# Radio.net
KiCad netlist of a schematic drawn in Altium Designer
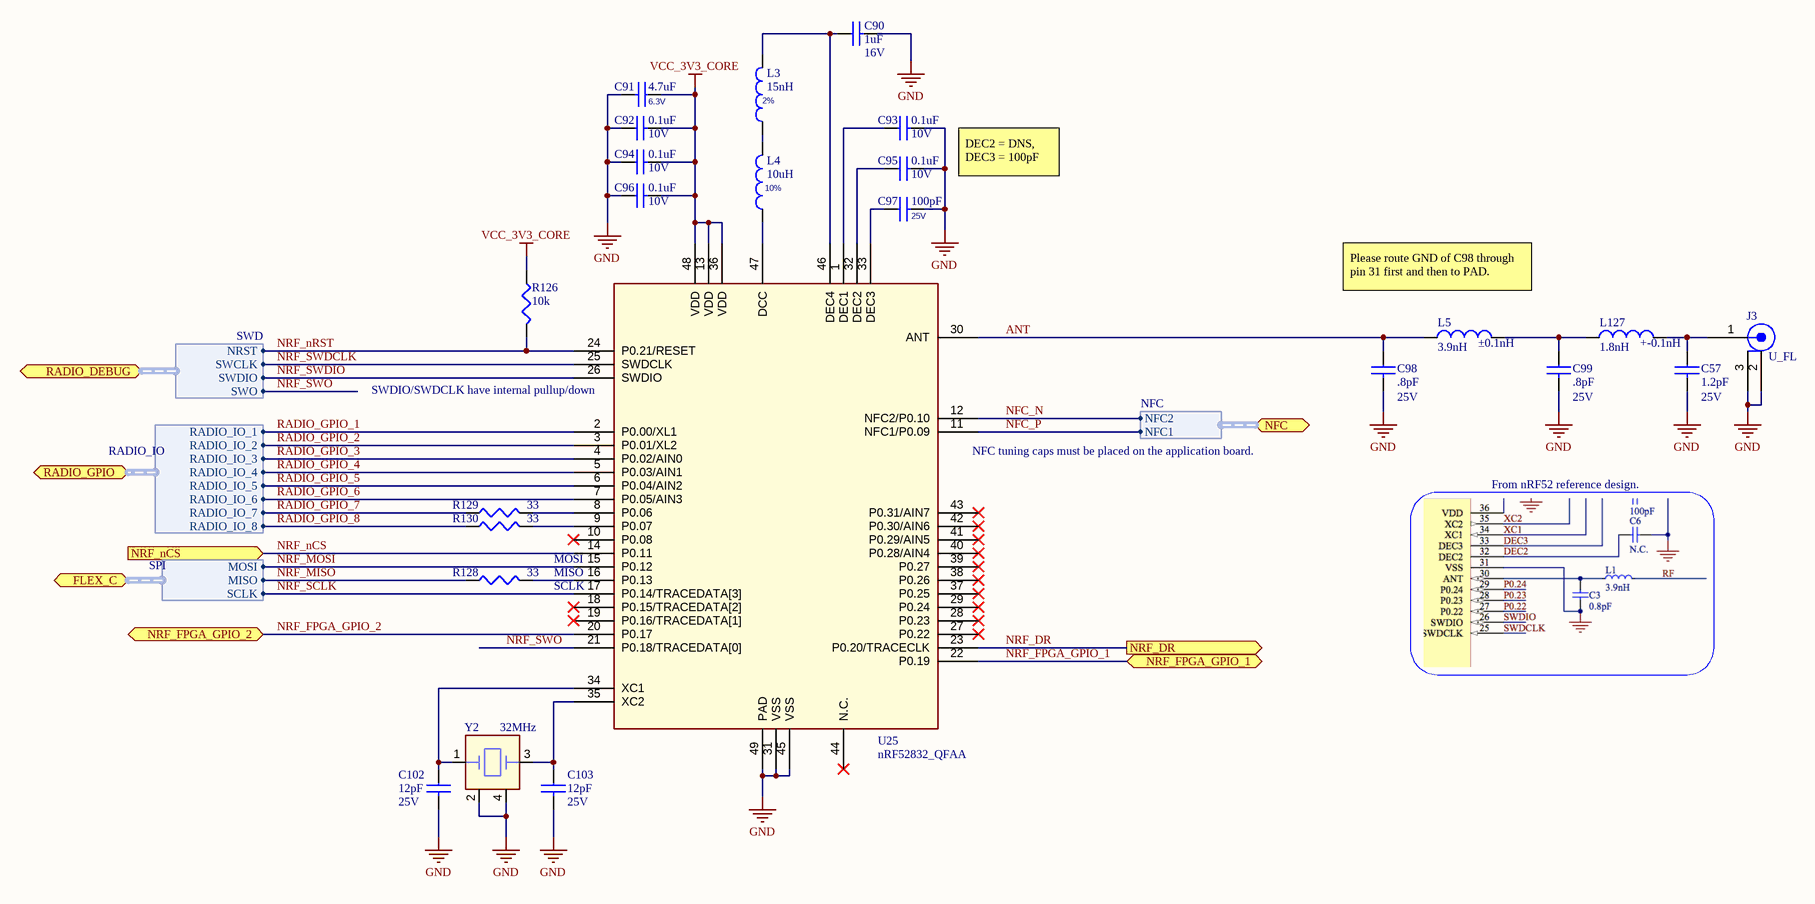
[diagram p0: Radio.SchDoc]

(export (version "E")
  (design (tool "Eeschema 10.0.6"))
  (components
    (comp (ref "C57")
      (value "1.2pF")
      (footprint "0201-IPCsm_33")
      (description "Multilayer Ceramic Capacitors MLCC - SMD/SMT 0201 1.2pF 25Volts C0G +/-0.1pF")
      (fields
        (field (name "VOLTAGE") "25V")
        (field (name "MFG") "Murata")
        (field (name "TOLERANCE") "±0.1pF")
      )
      (libsource (lib "SynapseLibrary") (part "CAP"))
    )
    (comp (ref "C90")
      (value "1uF")
      (footprint "0402-IPCsm_55")
      (description "CAP CER 1UF 16V X5R 0402")
      (fields
        (field (name "VOLTAGE") "16V")
        (field (name "MFG") "Samsung Electro-Mechanics America, Inc.")
        (field (name "TOLERANCE") "1%")
      )
      (libsource (lib "SynapseLibrary") (part "CAP"))
    )
    (comp (ref "C91")
      (value "4.7uF")
      (footprint "0402-IPCsm_55")
      (description "CAP CER 4.7UF 6.3V 20% X5R 0402")
      (fields (field (name "VOLTAGE") "6.3V") (field (name "MFG") "MURATA") (field (name "TOLERANCE") "20%"))
      (libsource (lib "SynapseLibrary") (part "CAP"))
    )
    (comp (ref "C92")
      (value "0.1uF")
      (footprint "0201-IPCsm_33")
      (description "CAP CER 0.1UF 10V 10% X5R 0201")
      (fields
        (field (name "VOLTAGE") "10V")
        (field (name "MFG") "Samsung Electro-Mechanics America, Inc")
        (field (name "TOLERANCE") "10%")
      )
      (libsource (lib "SynapseLibrary") (part "CAP"))
    )
    (comp (ref "C93")
      (value "0.1uF")
      (footprint "0201-IPCsm_33")
      (description "CAP CER 0.1UF 10V 10% X5R 0201")
      (fields
        (field (name "VOLTAGE") "10V")
        (field (name "MFG") "Samsung Electro-Mechanics America, Inc")
        (field (name "TOLERANCE") "10%")
      )
      (libsource (lib "SynapseLibrary") (part "CAP"))
    )
    (comp (ref "C94")
      (value "0.1uF")
      (footprint "0201-IPCsm_33")
      (description "CAP CER 0.1UF 10V 10% X5R 0201")
      (fields
        (field (name "VOLTAGE") "10V")
        (field (name "MFG") "Samsung Electro-Mechanics America, Inc")
        (field (name "TOLERANCE") "10%")
      )
      (libsource (lib "SynapseLibrary") (part "CAP"))
    )
    (comp (ref "C95")
      (value "0.1uF")
      (footprint "0201-IPCsm_33")
      (description "CAP CER 0.1UF 10V 10% X5R 0201")
      (fields
        (field (name "VOLTAGE") "10V")
        (field (name "MFG") "Samsung Electro-Mechanics America, Inc")
        (field (name "TOLERANCE") "10%")
      )
      (libsource (lib "SynapseLibrary") (part "CAP"))
    )
    (comp (ref "C96")
      (value "0.1uF")
      (footprint "0201-IPCsm_33")
      (description "CAP CER 0.1UF 10V 10% X5R 0201")
      (fields
        (field (name "VOLTAGE") "10V")
        (field (name "MFG") "Samsung Electro-Mechanics America, Inc")
        (field (name "TOLERANCE") "10%")
      )
      (libsource (lib "SynapseLibrary") (part "CAP"))
    )
    (comp (ref "C97")
      (value "100pF")
      (footprint "0201-IPCsm_33")
      (description "CAP CER 100PF 25V 5% NP0 0201")
      (fields (field (name "VOLTAGE") "25V") (field (name "MFG") "MURATA") (field (name "TOLERANCE") "5%"))
      (libsource (lib "SynapseLibrary") (part "CAP"))
    )
    (comp (ref "C98")
      (value ".8pF")
      (footprint "0201-IPCsm_33")
      (fields
        (field (name "VOLTAGE") "25V")
        (field (name "MFG") "Murata Electronics North America")
        (field (name "TOLERANCE") "0.05pF")
      )
      (libsource (lib "SynapseLibrary") (part "CAP"))
    )
    (comp (ref "C99")
      (value ".8pF")
      (footprint "0201-IPCsm_33")
      (description "CAP CER 0.8PF 25V NP0 0201")
      (fields
        (field (name "VOLTAGE") "25V")
        (field (name "MFG") "TDK Corporation")
        (field (name "TOLERANCE") "0.05pF")
      )
      (libsource (lib "SynapseLibrary") (part "CAP"))
    )
    (comp (ref "C102")
      (value "12pF")
      (footprint "0201-IPCsm_33")
      (description "12pF 25V Ceramic Capacitor C0G, NP0 0201")
      (fields (field (name "VOLTAGE") "25V") (field (name "MFG") "Murata") (field (name "TOLERANCE") "2%"))
      (libsource (lib "SynapseLibrary") (part "CAP"))
    )
    (comp (ref "C103")
      (value "12pF")
      (footprint "0201-IPCsm_33")
      (description "12pF 25V Ceramic Capacitor C0G, NP0 0201")
      (fields (field (name "VOLTAGE") "25V") (field (name "MFG") "Murata") (field (name "TOLERANCE") "2%"))
      (libsource (lib "SynapseLibrary") (part "CAP"))
    )
    (comp (ref "J3")
      (value "U_FL")
      (footprint "con_hrs_U_FL-SMT")
      (description "CONN RECPT ULTRA-MINI COAX SMD")
      (fields (field (name "MFG") "HIROSE"))
      (libsource (lib "SynapseLibrary") (part "CONNECTOR COAX-M 2GND"))
    )
    (comp (ref "L3")
      (value "15nH")
      (footprint "IND_0402-36_LQP15M")
      (description "IND, 15 nH, 2%, 0402")
      (fields (field (name "TOLERANCE") "2%") (field (name "MFG") "Murata"))
      (libsource (lib "SynapseLibrary") (part "IND_H"))
    )
    (comp (ref "L4")
      (value "10uH")
      (footprint "IND-0603_32H")
      (description "INDUCTOR 10UH 115MA 0603")
      (fields (field (name "TOLERANCE") "10%") (field (name "MFG") "Taiyo Yuden"))
      (libsource (lib "SynapseLibrary") (part "IND_H"))
    )
    (comp (ref "L5")
      (value "3.9nH")
      (footprint "0201-IPCsm_33")
      (description "FIXED IND 3.9NH 400MA 300 MOHM 0201")
      (fields (field (name "TOLERANCE") "±0.1nH") (field (name "MFG") "Murata"))
      (libsource (lib "SynapseLibrary") (part "IND_H"))
    )
    (comp (ref "L127")
      (value "1.8nH")
      (footprint "0201-IPCsm_33")
      (description "FIXED IND 1.8NH 600MA 150 MOHM")
      (fields (field (name "TOLERANCE") "+-0.1nH") (field (name "MFG") "MURATA"))
      (libsource (lib "SynapseLibrary") (part "IND_H"))
    )
    (comp (ref "R126")
      (value "10k")
      (footprint "0201-IPCsm_26")
      (description "RES 10K OHM 1/20W 1% 0201 SMD")
      (fields (field (name "TOLERANCE") "1.00%") (field (name "VOLTAGE") "50V"))
      (libsource (lib "SynapseLibrary") (part "RES"))
    )
    (comp (ref "R128")
      (value "33")
      (footprint "0201-IPCsm_26")
      (description "RES 33 OHM 1/20W 1% 0201 SMD")
      (fields (field (name "TOLERANCE") "1.00%") (field (name "VOLTAGE") "50V"))
      (libsource (lib "SynapseLibrary") (part "RES"))
    )
    (comp (ref "R129")
      (value "33")
      (footprint "0201-IPCsm_26")
      (description "RES 33 OHM 1/20W 1% 0201 SMD")
      (fields (field (name "TOLERANCE") "1.00%") (field (name "VOLTAGE") "50V"))
      (libsource (lib "SynapseLibrary") (part "RES"))
    )
    (comp (ref "R130")
      (value "33")
      (footprint "0201-IPCsm_26")
      (description "RES 33 OHM 1/20W 1% 0201 SMD")
      (fields (field (name "TOLERANCE") "1.00%") (field (name "VOLTAGE") "50V"))
      (libsource (lib "SynapseLibrary") (part "RES"))
    )
    (comp (ref "U25")
      (value "nRF52832_QFAA")
      (footprint "QFN48_6X6MM_NO_VIAS")
      (description "IC SOC 2.4GHZ 512K FLASH QFN")
      (fields
        (field (name "PART NUMBER") "nRF52832-QFAA")
        (field (name "MANUFACTURER") "Nordic Semiconductor")
        (field (name "PUBLISHER") "Nordic Semiconductor")
      )
      (libsource (lib "SynapseLibrary") (part "nRF52832_QFAA"))
    )
    (comp (ref "Y2")
      (value "32MHz")
      (footprint "Xtal_abm12")
      (description "Crystal 32.0000MHz 20ppm 8pF 100 Ohm -20°C - 70°C Surface Mount 4-SMD, No Lead (DFN, LCC)")
      (fields (field (name "MFG") "Abracon LLC") (field (name "TOLERANCE") "20ppm"))
      (libsource (lib "SynapseLibrary") (part "XTAL_2_GND_PIN"))
    )
  )
  (nets
    (net (code "5") (name "/ANT") (class "Default")
      (node (ref "C98") (pin "1") (pinfunction "1_1") (pintype "passive"))
      (node (ref "L5") (pin "1") (pinfunction "1_1") (pintype "passive"))
      (node (ref "U25") (pin "30") (pinfunction "ANT_30") (pintype "passive"))
    )
    (net (code "6") (name "/NFC_N") (class "Default")
      (node (ref "U25") (pin "12") (pinfunction "NFC2/P0.10_12") (pintype "passive"))
    )
    (net (code "7") (name "/NFC_P") (class "Default")
      (node (ref "U25") (pin "11") (pinfunction "NFC1/P0.09_11") (pintype "passive"))
    )
    (net (code "8") (name "/NRF_DR") (class "Default")
      (node (ref "U25") (pin "23") (pinfunction "P0.20/TRACECLK_23") (pintype "passive"))
    )
    (net (code "9") (name "/NRF_FPGA_GPIO_1") (class "Default")
      (node (ref "U25") (pin "22") (pinfunction "P0.19_22") (pintype "passive"))
    )
    (net (code "10") (name "/NRF_FPGA_GPIO_2") (class "Default")
      (node (ref "U25") (pin "20") (pinfunction "P0.17_20") (pintype "passive"))
    )
    (net (code "11") (name "/NRF_MISO") (class "Default")
      (node (ref "R128") (pin "1") (pinfunction "1_1") (pintype "passive"))
    )
    (net (code "12") (name "/NRF_MOSI") (class "Default")
      (node (ref "U25") (pin "15") (pinfunction "P0.12_15") (pintype "passive"))
    )
    (net (code "13") (name "/NRF_SCLK") (class "Default")
      (node (ref "U25") (pin "17") (pinfunction "P0.14/TRACEDATA[3]_17") (pintype "passive"))
    )
    (net (code "14") (name "/NRF_SWDCLK") (class "Default")
      (node (ref "U25") (pin "25") (pinfunction "SWDCLK_25") (pintype "passive"))
    )
    (net (code "15") (name "/NRF_SWDIO") (class "Default")
      (node (ref "U25") (pin "26") (pinfunction "SWDIO_26") (pintype "passive"))
    )
    (net (code "16") (name "/NRF_SWO") (class "Default")
      (node (ref "U25") (pin "21") (pinfunction "P0.18/TRACEDATA[0]_21") (pintype "passive"))
    )
    (net (code "17") (name "/NRF_nCS") (class "Default")
      (node (ref "U25") (pin "14") (pinfunction "P0.11_14") (pintype "passive"))
    )
    (net (code "18") (name "/NRF_nRST") (class "Default")
      (node (ref "R126") (pin "2") (pinfunction "2_2") (pintype "passive"))
      (node (ref "U25") (pin "24") (pinfunction "P0.21/RESET_24") (pintype "passive"))
    )
    (net (code "19") (name "/RADIO_GPIO_1") (class "Default")
      (node (ref "U25") (pin "2") (pinfunction "P0.00/XL1_2") (pintype "passive"))
    )
    (net (code "20") (name "/RADIO_GPIO_2") (class "Default")
      (node (ref "U25") (pin "3") (pinfunction "P0.01/XL2_3") (pintype "passive"))
    )
    (net (code "21") (name "/RADIO_GPIO_3") (class "Default")
      (node (ref "U25") (pin "4") (pinfunction "P0.02/AIN0_4") (pintype "passive"))
    )
    (net (code "22") (name "/RADIO_GPIO_4") (class "Default")
      (node (ref "U25") (pin "5") (pinfunction "P0.03/AIN1_5") (pintype "passive"))
    )
    (net (code "23") (name "/RADIO_GPIO_5") (class "Default")
      (node (ref "U25") (pin "6") (pinfunction "P0.04/AIN2_6") (pintype "passive"))
    )
    (net (code "24") (name "/RADIO_GPIO_6") (class "Default")
      (node (ref "U25") (pin "7") (pinfunction "P0.05/AIN3_7") (pintype "passive"))
    )
    (net (code "25") (name "/RADIO_GPIO_7") (class "Default")
      (node (ref "R129") (pin "1") (pinfunction "1_1") (pintype "passive"))
    )
    (net (code "26") (name "/RADIO_GPIO_8") (class "Default")
      (node (ref "R130") (pin "1") (pinfunction "1_1") (pintype "passive"))
    )
    (net (code "31") (name "GND") (class "Default")
      (node (ref "C102") (pin "2") (pinfunction "2_2") (pintype "passive"))
      (node (ref "C103") (pin "2") (pinfunction "2_2") (pintype "passive"))
      (node (ref "C57") (pin "2") (pinfunction "2_2") (pintype "passive"))
      (node (ref "C90") (pin "2") (pinfunction "2_2") (pintype "passive"))
      (node (ref "C91") (pin "2") (pinfunction "2_2") (pintype "passive"))
      (node (ref "C92") (pin "1") (pinfunction "1_1") (pintype "passive"))
      (node (ref "C93") (pin "2") (pinfunction "2_2") (pintype "passive"))
      (node (ref "C94") (pin "1") (pinfunction "1_1") (pintype "passive"))
      (node (ref "C95") (pin "2") (pinfunction "2_2") (pintype "passive"))
      (node (ref "C96") (pin "1") (pinfunction "1_1") (pintype "passive"))
      (node (ref "C97") (pin "2") (pinfunction "2_2") (pintype "passive"))
      (node (ref "C98") (pin "2") (pinfunction "2_2") (pintype "passive"))
      (node (ref "C99") (pin "2") (pinfunction "2_2") (pintype "passive"))
      (node (ref "J3") (pin "2") (pinfunction "SHIELD_2") (pintype "passive"))
      (node (ref "J3") (pin "3") (pinfunction "SHIELD2_3") (pintype "passive"))
      (node (ref "U25") (pin "31") (pinfunction "VSS_31") (pintype "passive"))
      (node (ref "U25") (pin "45") (pinfunction "VSS_45") (pintype "passive"))
      (node (ref "U25") (pin "49") (pinfunction "PAD_49") (pintype "passive"))
      (node (ref "Y2") (pin "2") (pinfunction "2_2") (pintype "passive"))
      (node (ref "Y2") (pin "4") (pinfunction "4_4") (pintype "passive"))
    )
    (net (code "32") (name "Net-(C99-Pad1)") (class "Default")
      (node (ref "C99") (pin "1") (pinfunction "1_1") (pintype "passive"))
      (node (ref "L127") (pin "1") (pinfunction "1_1") (pintype "passive"))
      (node (ref "L5") (pin "2") (pinfunction "2_2") (pintype "passive"))
    )
    (net (code "33") (name "Net-(J3-CENTER)") (class "Default")
      (node (ref "C57") (pin "1") (pinfunction "1_1") (pintype "passive"))
      (node (ref "J3") (pin "1") (pinfunction "CENTER_1") (pintype "passive"))
      (node (ref "L127") (pin "2") (pinfunction "2_2") (pintype "passive"))
    )
    (net (code "34") (name "Net-(L3-Pad1)") (class "Default")
      (node (ref "L3") (pin "1") (pinfunction "1_1") (pintype "passive"))
      (node (ref "L4") (pin "2") (pinfunction "2_2") (pintype "passive"))
    )
    (net (code "35") (name "Net-(U25-DCC)") (class "Default")
      (node (ref "L4") (pin "1") (pinfunction "1_1") (pintype "passive"))
      (node (ref "U25") (pin "47") (pinfunction "DCC_47") (pintype "passive"))
    )
    (net (code "36") (name "Net-(U25-DEC1)") (class "Default")
      (node (ref "C93") (pin "1") (pinfunction "1_1") (pintype "passive"))
      (node (ref "U25") (pin "1") (pinfunction "DEC1_1") (pintype "passive"))
    )
    (net (code "37") (name "Net-(U25-DEC2)") (class "Default")
      (node (ref "C95") (pin "1") (pinfunction "1_1") (pintype "passive"))
      (node (ref "U25") (pin "32") (pinfunction "DEC2_32") (pintype "passive"))
    )
    (net (code "38") (name "Net-(U25-DEC3)") (class "Default")
      (node (ref "C97") (pin "1") (pinfunction "1_1") (pintype "passive"))
      (node (ref "U25") (pin "33") (pinfunction "DEC3_33") (pintype "passive"))
    )
    (net (code "39") (name "Net-(U25-DEC4)") (class "Default")
      (node (ref "C90") (pin "1") (pinfunction "1_1") (pintype "passive"))
      (node (ref "L3") (pin "2") (pinfunction "2_2") (pintype "passive"))
      (node (ref "U25") (pin "46") (pinfunction "DEC4_46") (pintype "passive"))
    )
    (net (code "40") (name "Net-(U25-P0.06)") (class "Default")
      (node (ref "R129") (pin "2") (pinfunction "2_2") (pintype "passive"))
      (node (ref "U25") (pin "8") (pinfunction "P0.06_8") (pintype "passive"))
    )
    (net (code "41") (name "Net-(U25-P0.07)") (class "Default")
      (node (ref "R130") (pin "2") (pinfunction "2_2") (pintype "passive"))
      (node (ref "U25") (pin "9") (pinfunction "P0.07_9") (pintype "passive"))
    )
    (net (code "42") (name "Net-(U25-P0.13)") (class "Default")
      (node (ref "R128") (pin "2") (pinfunction "2_2") (pintype "passive"))
      (node (ref "U25") (pin "16") (pinfunction "P0.13_16") (pintype "passive"))
    )
    (net (code "43") (name "Net-(U25-XC1)") (class "Default")
      (node (ref "C102") (pin "1") (pinfunction "1_1") (pintype "passive"))
      (node (ref "U25") (pin "34") (pinfunction "XC1_34") (pintype "passive"))
      (node (ref "Y2") (pin "1") (pinfunction "1_1") (pintype "passive"))
    )
    (net (code "44") (name "Net-(U25-XC2)") (class "Default")
      (node (ref "C103") (pin "1") (pinfunction "1_1") (pintype "passive"))
      (node (ref "U25") (pin "35") (pinfunction "XC2_35") (pintype "passive"))
      (node (ref "Y2") (pin "3") (pinfunction "3_3") (pintype "passive"))
    )
    (net (code "45") (name "VCC_3V3_CORE") (class "Default")
      (node (ref "C91") (pin "1") (pinfunction "1_1") (pintype "passive"))
      (node (ref "C92") (pin "2") (pinfunction "2_2") (pintype "passive"))
      (node (ref "C94") (pin "2") (pinfunction "2_2") (pintype "passive"))
      (node (ref "C96") (pin "2") (pinfunction "2_2") (pintype "passive"))
      (node (ref "R126") (pin "1") (pinfunction "1_1") (pintype "passive"))
      (node (ref "U25") (pin "13") (pinfunction "VDD_13") (pintype "passive"))
      (node (ref "U25") (pin "36") (pinfunction "VDD_36") (pintype "passive"))
      (node (ref "U25") (pin "48") (pinfunction "VDD_48") (pintype "passive"))
    )
    (net (code "46") (name "unconnected-(U25-N.C.-Pad44)") (class "Default")
      (node (ref "U25") (pin "44") (pinfunction "N.C._44") (pintype "passive+no_connect"))
    )
    (net (code "47") (name "unconnected-(U25-P0.08-Pad10)") (class "Default")
      (node (ref "U25") (pin "10") (pinfunction "P0.08_10") (pintype "passive+no_connect"))
    )
    (net (code "48") (name "unconnected-(U25-P0.15{slash}TRACEDATA[2]-Pad18)") (class "Default")
      (node (ref "U25") (pin "18") (pinfunction "P0.15/TRACEDATA[2]_18") (pintype "passive+no_connect"))
    )
    (net (code "49") (name "unconnected-(U25-P0.16{slash}TRACEDATA[1]-Pad19)") (class "Default")
      (node (ref "U25") (pin "19") (pinfunction "P0.16/TRACEDATA[1]_19") (pintype "passive+no_connect"))
    )
    (net (code "50") (name "unconnected-(U25-P0.22-Pad27)") (class "Default")
      (node (ref "U25") (pin "27") (pinfunction "P0.22_27") (pintype "passive+no_connect"))
    )
    (net (code "51") (name "unconnected-(U25-P0.23-Pad28)") (class "Default")
      (node (ref "U25") (pin "28") (pinfunction "P0.23_28") (pintype "passive+no_connect"))
    )
    (net (code "52") (name "unconnected-(U25-P0.24-Pad29)") (class "Default")
      (node (ref "U25") (pin "29") (pinfunction "P0.24_29") (pintype "passive+no_connect"))
    )
    (net (code "53") (name "unconnected-(U25-P0.25-Pad37)") (class "Default")
      (node (ref "U25") (pin "37") (pinfunction "P0.25_37") (pintype "passive+no_connect"))
    )
    (net (code "54") (name "unconnected-(U25-P0.26-Pad38)") (class "Default")
      (node (ref "U25") (pin "38") (pinfunction "P0.26_38") (pintype "passive+no_connect"))
    )
    (net (code "55") (name "unconnected-(U25-P0.27-Pad39)") (class "Default")
      (node (ref "U25") (pin "39") (pinfunction "P0.27_39") (pintype "passive+no_connect"))
    )
    (net (code "56") (name "unconnected-(U25-P0.28{slash}AIN4-Pad40)") (class "Default")
      (node (ref "U25") (pin "40") (pinfunction "P0.28/AIN4_40") (pintype "passive+no_connect"))
    )
    (net (code "57") (name "unconnected-(U25-P0.29{slash}AIN5-Pad41)") (class "Default")
      (node (ref "U25") (pin "41") (pinfunction "P0.29/AIN5_41") (pintype "passive+no_connect"))
    )
    (net (code "58") (name "unconnected-(U25-P0.30{slash}AIN6-Pad42)") (class "Default")
      (node (ref "U25") (pin "42") (pinfunction "P0.30/AIN6_42") (pintype "passive+no_connect"))
    )
    (net (code "59") (name "unconnected-(U25-P0.31{slash}AIN7-Pad43)") (class "Default")
      (node (ref "U25") (pin "43") (pinfunction "P0.31/AIN7_43") (pintype "passive+no_connect"))
    )
  )
)
